# TinyTX4.net
KiCad netlist of a schematic drawn in EAGLE
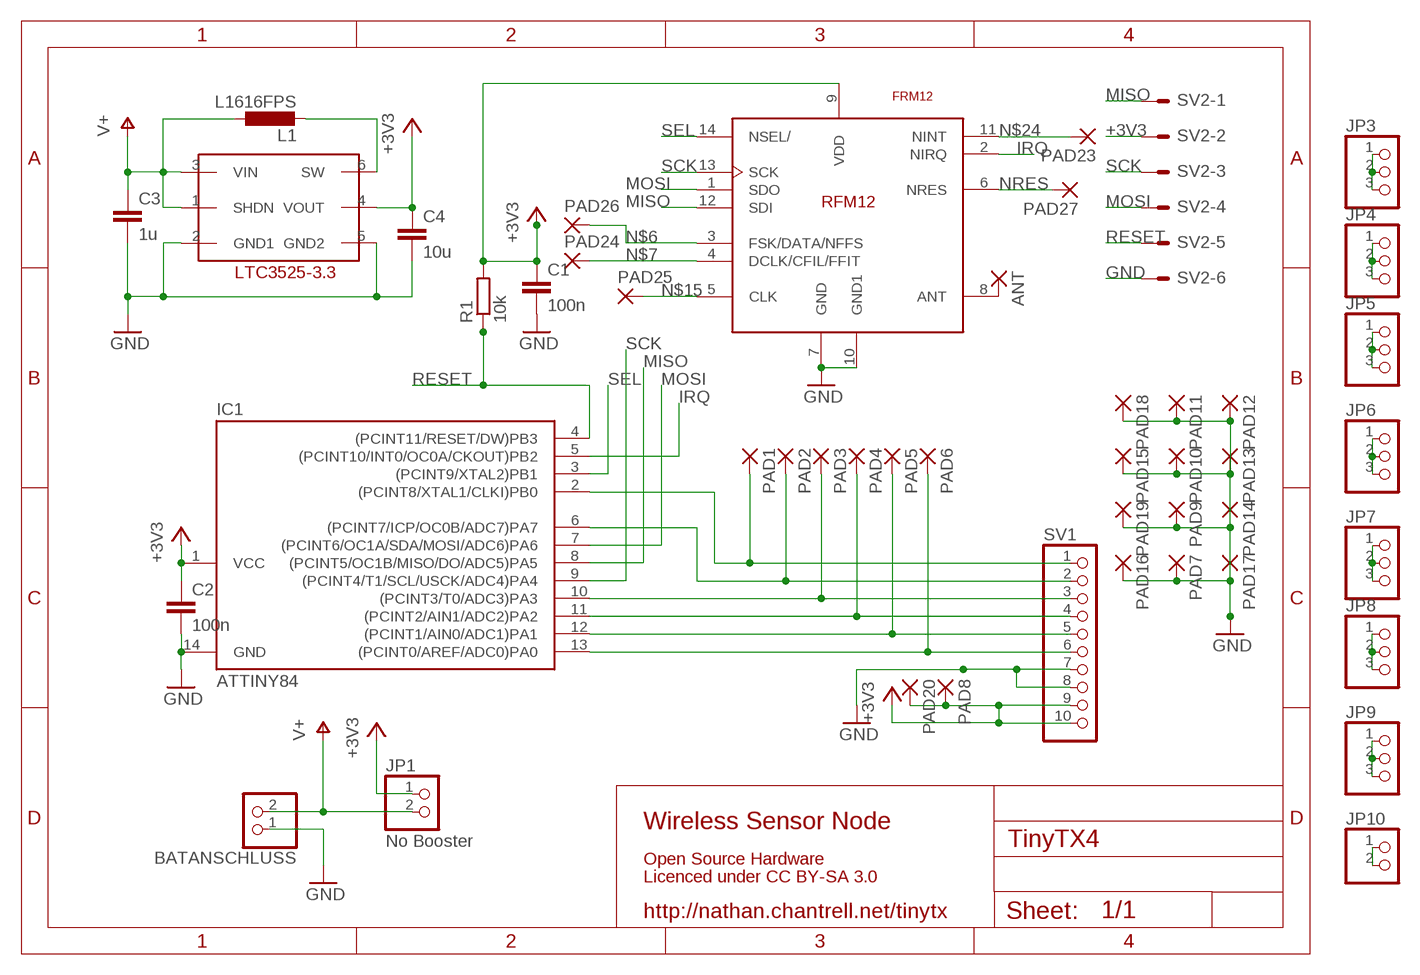
[diagram p0: schematic, sheet 1]

(export (version "E")
  (design (tool "Eeschema 10.0.6"))
  (components
    (comp (ref "ANT")
      (value "1,6/0,8")
      (footprint "eagle-import:1,6_0,8")
      (libsource (lib "eagle-import") (part "1,6/0,8"))
    )
    (comp (ref "BATANSCHLUSS")
      (value "PINHD-1X2")
      (footprint "eagle-import:1X02")
      (libsource (lib "eagle-import") (part "PINHD-1X2"))
    )
    (comp (ref "C1")
      (value "100n")
      (footprint "eagle-import:C0805")
      (libsource (lib "eagle-import") (part "C-EUC0805"))
    )
    (comp (ref "C2")
      (value "100n")
      (footprint "eagle-import:C0805")
      (libsource (lib "eagle-import") (part "C-EUC0805"))
    )
    (comp (ref "C3")
      (value "1u")
      (footprint "eagle-import:C0805")
      (libsource (lib "eagle-import") (part "C-EUC0805"))
    )
    (comp (ref "C4")
      (value "10u")
      (footprint "eagle-import:C0805")
      (libsource (lib "eagle-import") (part "C-EUC0805"))
    )
    (comp (ref "IC1")
      (value "ATTINY84")
      (footprint "eagle-import:SOIC14")
      (libsource (lib "eagle-import") (part "TINY24/44/84-SSU"))
    )
    (comp (ref "IC2")
      (value "IC2")
      (footprint "eagle-import:SC70-6")
      (libsource (lib "eagle-import") (part "LTC3525"))
    )
    (comp (ref "JP1")
      (value "No Booster")
      (footprint "eagle-import:1X02")
      (libsource (lib "eagle-import") (part "PINHD-1X2"))
    )
    (comp (ref "JP3")
      (value "PINHD-1X3")
      (footprint "eagle-import:1X03")
      (libsource (lib "eagle-import") (part "PINHD-1X3"))
    )
    (comp (ref "JP4")
      (value "PINHD-1X3")
      (footprint "eagle-import:1X03")
      (libsource (lib "eagle-import") (part "PINHD-1X3"))
    )
    (comp (ref "JP5")
      (value "PINHD-1X3")
      (footprint "eagle-import:1X03")
      (libsource (lib "eagle-import") (part "PINHD-1X3"))
    )
    (comp (ref "JP6")
      (value "PINHD-1X3")
      (footprint "eagle-import:1X03")
      (libsource (lib "eagle-import") (part "PINHD-1X3"))
    )
    (comp (ref "JP7")
      (value "PINHD-1X3")
      (footprint "eagle-import:1X03")
      (libsource (lib "eagle-import") (part "PINHD-1X3"))
    )
    (comp (ref "JP8")
      (value "PINHD-1X3")
      (footprint "eagle-import:1X03")
      (libsource (lib "eagle-import") (part "PINHD-1X3"))
    )
    (comp (ref "JP9")
      (value "PINHD-1X3")
      (footprint "eagle-import:1X03")
      (libsource (lib "eagle-import") (part "PINHD-1X3"))
    )
    (comp (ref "JP10")
      (value "PINHD-1X2")
      (footprint "eagle-import:1X02")
      (libsource (lib "eagle-import") (part "PINHD-1X2"))
    )
    (comp (ref "L1")
      (value "L1616FPS")
      (footprint "eagle-import:L1616")
      (libsource (lib "eagle-import") (part "L1616FPS"))
    )
    (comp (ref "PAD1")
      (value "1,6/0,9")
      (footprint "eagle-import:1,6_0,9")
      (libsource (lib "eagle-import") (part "1,6/0,9"))
    )
    (comp (ref "PAD2")
      (value "1,6/0,9")
      (footprint "eagle-import:1,6_0,9")
      (libsource (lib "eagle-import") (part "1,6/0,9"))
    )
    (comp (ref "PAD3")
      (value "1,6/0,9")
      (footprint "eagle-import:1,6_0,9")
      (libsource (lib "eagle-import") (part "1,6/0,9"))
    )
    (comp (ref "PAD4")
      (value "1,6/0,9")
      (footprint "eagle-import:1,6_0,9")
      (libsource (lib "eagle-import") (part "1,6/0,9"))
    )
    (comp (ref "PAD5")
      (value "1,6/0,9")
      (footprint "eagle-import:1,6_0,9")
      (libsource (lib "eagle-import") (part "1,6/0,9"))
    )
    (comp (ref "PAD6")
      (value "1,6/0,9")
      (footprint "eagle-import:1,6_0,9")
      (libsource (lib "eagle-import") (part "1,6/0,9"))
    )
    (comp (ref "PAD7")
      (value "1,6/0,9")
      (footprint "eagle-import:1,6_0,9")
      (libsource (lib "eagle-import") (part "1,6/0,9"))
    )
    (comp (ref "PAD8")
      (value "1,6/0,9")
      (footprint "eagle-import:1,6_0,9")
      (libsource (lib "eagle-import") (part "1,6/0,9"))
    )
    (comp (ref "PAD9")
      (value "1,6/0,9")
      (footprint "eagle-import:1,6_0,9")
      (libsource (lib "eagle-import") (part "1,6/0,9"))
    )
    (comp (ref "PAD10")
      (value "1,6/0,9")
      (footprint "eagle-import:1,6_0,9")
      (libsource (lib "eagle-import") (part "1,6/0,9"))
    )
    (comp (ref "PAD11")
      (value "1,6/0,9")
      (footprint "eagle-import:1,6_0,9")
      (libsource (lib "eagle-import") (part "1,6/0,9"))
    )
    (comp (ref "PAD12")
      (value "1,6/0,9")
      (footprint "eagle-import:1,6_0,9")
      (libsource (lib "eagle-import") (part "1,6/0,9"))
    )
    (comp (ref "PAD13")
      (value "1,6/0,9")
      (footprint "eagle-import:1,6_0,9")
      (libsource (lib "eagle-import") (part "1,6/0,9"))
    )
    (comp (ref "PAD14")
      (value "1,6/0,9")
      (footprint "eagle-import:1,6_0,9")
      (libsource (lib "eagle-import") (part "1,6/0,9"))
    )
    (comp (ref "PAD15")
      (value "1,6/0,9")
      (footprint "eagle-import:1,6_0,9")
      (libsource (lib "eagle-import") (part "1,6/0,9"))
    )
    (comp (ref "PAD16")
      (value "1,6/0,9")
      (footprint "eagle-import:1,6_0,9")
      (libsource (lib "eagle-import") (part "1,6/0,9"))
    )
    (comp (ref "PAD17")
      (value "1,6/0,9")
      (footprint "eagle-import:1,6_0,9")
      (libsource (lib "eagle-import") (part "1,6/0,9"))
    )
    (comp (ref "PAD18")
      (value "1,6/0,9")
      (footprint "eagle-import:1,6_0,9")
      (libsource (lib "eagle-import") (part "1,6/0,9"))
    )
    (comp (ref "PAD19")
      (value "1,6/0,9")
      (footprint "eagle-import:1,6_0,9")
      (libsource (lib "eagle-import") (part "1,6/0,9"))
    )
    (comp (ref "PAD20")
      (value "1,6/0,9")
      (footprint "eagle-import:1,6_0,9")
      (libsource (lib "eagle-import") (part "1,6/0,9"))
    )
    (comp (ref "PAD23")
      (value "1,6/0,9")
      (footprint "eagle-import:1,6_0,9")
      (libsource (lib "eagle-import") (part "1,6/0,9"))
    )
    (comp (ref "PAD24")
      (value "1,6/0,9")
      (footprint "eagle-import:1,6_0,9")
      (libsource (lib "eagle-import") (part "1,6/0,9"))
    )
    (comp (ref "PAD25")
      (value "1,6/0,9")
      (footprint "eagle-import:1,6_0,9")
      (libsource (lib "eagle-import") (part "1,6/0,9"))
    )
    (comp (ref "PAD26")
      (value "1,6/0,9")
      (footprint "eagle-import:1,6_0,9")
      (libsource (lib "eagle-import") (part "1,6/0,9"))
    )
    (comp (ref "PAD27")
      (value "1,6/0,9")
      (footprint "eagle-import:1,6_0,9")
      (libsource (lib "eagle-import") (part "1,6/0,9"))
    )
    (comp (ref "R1")
      (value "10k")
      (footprint "eagle-import:R0805")
      (libsource (lib "eagle-import") (part "R-EU_R0805"))
    )
    (comp (ref "SV1")
      (value "PINHD-1X10")
      (footprint "eagle-import:1X10")
      (libsource (lib "eagle-import") (part "PINHD-1X10"))
    )
    (comp (ref "SV2")
      (value "ML6E")
      (footprint "eagle-import:ML6")
      (libsource (lib "eagle-import") (part "ML6?E"))
    )
    (comp (ref "U$3")
      (value "FRM12")
      (footprint "eagle-import:RFM12")
      (libsource (lib "eagle-import") (part "FRM12"))
    )
  )
  (nets
    (net (code "1") (name "+3V3") (class "Default")
      (node (ref "C1") (pin "1") (pinfunction "1_1") (pintype "passive"))
      (node (ref "C2") (pin "1") (pinfunction "1_1") (pintype "passive"))
      (node (ref "C4") (pin "1") (pinfunction "1_1") (pintype "passive"))
      (node (ref "IC1") (pin "1") (pinfunction "VCC_1") (pintype "power_in"))
      (node (ref "IC2") (pin "4") (pinfunction "VOUT_4") (pintype "bidirectional"))
      (node (ref "JP1") (pin "1") (pinfunction "1_1") (pintype "passive"))
      (node (ref "PAD20") (pin "1") (pinfunction "P_1") (pintype "passive"))
      (node (ref "PAD8") (pin "1") (pinfunction "P_1") (pintype "passive"))
      (node (ref "R1") (pin "2") (pinfunction "2_2") (pintype "passive"))
      (node (ref "SV1") (pin "10") (pinfunction "10_10") (pintype "passive"))
      (node (ref "SV1") (pin "9") (pinfunction "9_9") (pintype "passive"))
      (node (ref "SV2") (pin "2") (pinfunction "S_2") (pintype "passive"))
      (node (ref "U$3") (pin "9") (pinfunction "VDD_9") (pintype "power_in"))
    )
    (net (code "2") (name "/IRQ") (class "Default")
      (node (ref "IC1") (pin "5") (pinfunction "(PCINT10/INT0/OC0A/CKOUT)PB2_5") (pintype "bidirectional"))
      (node (ref "U$3") (pin "2") (pinfunction "NIRQ_2") (pintype "output"))
    )
    (net (code "3") (name "/MISO") (class "Default")
      (node (ref "IC1") (pin "8") (pinfunction "(PCINT5/OC1B/MISO/DO/ADC5)PA5_8") (pintype "bidirectional"))
      (node (ref "SV2") (pin "1") (pinfunction "S_1") (pintype "passive"))
      (node (ref "U$3") (pin "12") (pinfunction "SDI_12") (pintype "input"))
    )
    (net (code "4") (name "/MOSI") (class "Default")
      (node (ref "IC1") (pin "7") (pinfunction "(PCINT6/OC1A/SDA/MOSI/ADC6)PA6_7") (pintype "bidirectional"))
      (node (ref "SV2") (pin "4") (pinfunction "S_4") (pintype "passive"))
      (node (ref "U$3") (pin "1") (pinfunction "SDO_1") (pintype "output"))
    )
    (net (code "5") (name "/N$6") (class "Default")
      (node (ref "PAD26") (pin "1") (pinfunction "P_1") (pintype "passive"))
      (node (ref "U$3") (pin "3") (pinfunction "FSK/DATA/NFFS_3") (pintype "bidirectional"))
    )
    (net (code "6") (name "/N$7") (class "Default")
      (node (ref "PAD24") (pin "1") (pinfunction "P_1") (pintype "passive"))
      (node (ref "U$3") (pin "4") (pinfunction "DCLK/CFIL/FFIT_4") (pintype "bidirectional"))
    )
    (net (code "7") (name "/N$15") (class "Default")
      (node (ref "PAD25") (pin "1") (pinfunction "P_1") (pintype "passive"))
      (node (ref "U$3") (pin "5") (pinfunction "CLK_5") (pintype "output"))
    )
    (net (code "8") (name "/N$24") (class "Default")
      (node (ref "PAD23") (pin "1") (pinfunction "P_1") (pintype "passive"))
      (node (ref "U$3") (pin "11") (pinfunction "NINT_11") (pintype "bidirectional"))
    )
    (net (code "9") (name "/NRES") (class "Default")
      (node (ref "PAD27") (pin "1") (pinfunction "P_1") (pintype "passive"))
      (node (ref "U$3") (pin "6") (pinfunction "NRES_6") (pintype "bidirectional"))
    )
    (net (code "10") (name "/RESET") (class "Default")
      (node (ref "IC1") (pin "4") (pinfunction "(PCINT11/RESET/DW)PB3_4") (pintype "bidirectional"))
      (node (ref "R1") (pin "1") (pinfunction "1_1") (pintype "passive"))
      (node (ref "SV2") (pin "5") (pinfunction "S_5") (pintype "passive"))
    )
    (net (code "11") (name "/SCK") (class "Default")
      (node (ref "IC1") (pin "9") (pinfunction "(PCINT4/T1/SCL/USCK/ADC4)PA4_9") (pintype "bidirectional"))
      (node (ref "SV2") (pin "3") (pinfunction "S_3") (pintype "passive"))
      (node (ref "U$3") (pin "13") (pinfunction "SCK_13") (pintype "input"))
    )
    (net (code "12") (name "/SEL") (class "Default")
      (node (ref "IC1") (pin "3") (pinfunction "(PCINT9/XTAL2)PB1_3") (pintype "bidirectional"))
      (node (ref "U$3") (pin "14") (pinfunction "NSEL/_14") (pintype "input"))
    )
    (net (code "13") (name "GND") (class "Default")
      (node (ref "BATANSCHLUSS") (pin "1") (pinfunction "1_1") (pintype "passive"))
      (node (ref "C1") (pin "2") (pinfunction "2_2") (pintype "passive"))
      (node (ref "C2") (pin "2") (pinfunction "2_2") (pintype "passive"))
      (node (ref "C3") (pin "2") (pinfunction "2_2") (pintype "passive"))
      (node (ref "C4") (pin "2") (pinfunction "2_2") (pintype "passive"))
      (node (ref "IC1") (pin "14") (pinfunction "GND_14") (pintype "power_in"))
      (node (ref "IC2") (pin "2") (pinfunction "GND1_2") (pintype "bidirectional"))
      (node (ref "IC2") (pin "5") (pinfunction "GND2_5") (pintype "bidirectional"))
      (node (ref "PAD10") (pin "1") (pinfunction "P_1") (pintype "passive"))
      (node (ref "PAD11") (pin "1") (pinfunction "P_1") (pintype "passive"))
      (node (ref "PAD12") (pin "1") (pinfunction "P_1") (pintype "passive"))
      (node (ref "PAD13") (pin "1") (pinfunction "P_1") (pintype "passive"))
      (node (ref "PAD14") (pin "1") (pinfunction "P_1") (pintype "passive"))
      (node (ref "PAD15") (pin "1") (pinfunction "P_1") (pintype "passive"))
      (node (ref "PAD16") (pin "1") (pinfunction "P_1") (pintype "passive"))
      (node (ref "PAD17") (pin "1") (pinfunction "P_1") (pintype "passive"))
      (node (ref "PAD18") (pin "1") (pinfunction "P_1") (pintype "passive"))
      (node (ref "PAD19") (pin "1") (pinfunction "P_1") (pintype "passive"))
      (node (ref "PAD7") (pin "1") (pinfunction "P_1") (pintype "passive"))
      (node (ref "PAD9") (pin "1") (pinfunction "P_1") (pintype "passive"))
      (node (ref "SV1") (pin "7") (pinfunction "7_7") (pintype "passive"))
      (node (ref "SV1") (pin "8") (pinfunction "8_8") (pintype "passive"))
      (node (ref "SV2") (pin "6") (pinfunction "S_6") (pintype "passive"))
      (node (ref "U$3") (pin "10") (pinfunction "GND1_10") (pintype "passive"))
      (node (ref "U$3") (pin "7") (pinfunction "GND_7") (pintype "passive"))
    )
    (net (code "14") (name "Net-(ANT-P)") (class "Default")
      (node (ref "ANT") (pin "1") (pinfunction "P_1") (pintype "passive"))
      (node (ref "U$3") (pin "8") (pinfunction "ANT_8") (pintype "bidirectional"))
    )
    (net (code "15") (name "Net-(IC1-(PCINT0{slash}AREF{slash}ADC0)PA0)") (class "Default")
      (node (ref "IC1") (pin "13") (pinfunction "(PCINT0/AREF/ADC0)PA0_13") (pintype "bidirectional"))
      (node (ref "PAD6") (pin "1") (pinfunction "P_1") (pintype "passive"))
      (node (ref "SV1") (pin "6") (pinfunction "6_6") (pintype "passive"))
    )
    (net (code "16") (name "Net-(IC1-(PCINT1{slash}AIN0{slash}ADC1)PA1)") (class "Default")
      (node (ref "IC1") (pin "12") (pinfunction "(PCINT1/AIN0/ADC1)PA1_12") (pintype "bidirectional"))
      (node (ref "PAD5") (pin "1") (pinfunction "P_1") (pintype "passive"))
      (node (ref "SV1") (pin "5") (pinfunction "5_5") (pintype "passive"))
    )
    (net (code "17") (name "Net-(IC1-(PCINT2{slash}AIN1{slash}ADC2)PA2)") (class "Default")
      (node (ref "IC1") (pin "11") (pinfunction "(PCINT2/AIN1/ADC2)PA2_11") (pintype "bidirectional"))
      (node (ref "PAD4") (pin "1") (pinfunction "P_1") (pintype "passive"))
      (node (ref "SV1") (pin "4") (pinfunction "4_4") (pintype "passive"))
    )
    (net (code "18") (name "Net-(IC1-(PCINT3{slash}T0{slash}ADC3)PA3)") (class "Default")
      (node (ref "IC1") (pin "10") (pinfunction "(PCINT3/T0/ADC3)PA3_10") (pintype "bidirectional"))
      (node (ref "PAD3") (pin "1") (pinfunction "P_1") (pintype "passive"))
      (node (ref "SV1") (pin "3") (pinfunction "3_3") (pintype "passive"))
    )
    (net (code "19") (name "Net-(IC1-(PCINT7{slash}ICP{slash}OC0B{slash}ADC7)PA7)") (class "Default")
      (node (ref "IC1") (pin "6") (pinfunction "(PCINT7/ICP/OC0B/ADC7)PA7_6") (pintype "bidirectional"))
      (node (ref "PAD2") (pin "1") (pinfunction "P_1") (pintype "passive"))
      (node (ref "SV1") (pin "2") (pinfunction "2_2") (pintype "passive"))
    )
    (net (code "20") (name "Net-(IC1-(PCINT8{slash}XTAL1{slash}CLKI)PB0)") (class "Default")
      (node (ref "IC1") (pin "2") (pinfunction "(PCINT8/XTAL1/CLKI)PB0_2") (pintype "bidirectional"))
      (node (ref "PAD1") (pin "1") (pinfunction "P_1") (pintype "passive"))
      (node (ref "SV1") (pin "1") (pinfunction "1_1") (pintype "passive"))
    )
    (net (code "21") (name "Net-(IC2-SW)") (class "Default")
      (node (ref "IC2") (pin "6") (pinfunction "SW_6") (pintype "bidirectional"))
      (node (ref "L1") (pin "P$2") (pinfunction "2_P$2") (pintype "passive"))
    )
    (net (code "22") (name "Net-(JP3-Pad1)") (class "Default")
      (node (ref "JP3") (pin "1") (pinfunction "1_1") (pintype "passive"))
      (node (ref "JP3") (pin "2") (pinfunction "2_2") (pintype "passive"))
      (node (ref "JP3") (pin "3") (pinfunction "3_3") (pintype "passive"))
    )
    (net (code "23") (name "Net-(JP4-Pad1)") (class "Default")
      (node (ref "JP4") (pin "1") (pinfunction "1_1") (pintype "passive"))
      (node (ref "JP4") (pin "2") (pinfunction "2_2") (pintype "passive"))
      (node (ref "JP4") (pin "3") (pinfunction "3_3") (pintype "passive"))
    )
    (net (code "24") (name "Net-(JP5-Pad1)") (class "Default")
      (node (ref "JP5") (pin "1") (pinfunction "1_1") (pintype "passive"))
      (node (ref "JP5") (pin "2") (pinfunction "2_2") (pintype "passive"))
      (node (ref "JP5") (pin "3") (pinfunction "3_3") (pintype "passive"))
    )
    (net (code "25") (name "Net-(JP6-Pad1)") (class "Default")
      (node (ref "JP6") (pin "1") (pinfunction "1_1") (pintype "passive"))
      (node (ref "JP6") (pin "2") (pinfunction "2_2") (pintype "passive"))
      (node (ref "JP6") (pin "3") (pinfunction "3_3") (pintype "passive"))
    )
    (net (code "26") (name "Net-(JP7-Pad1)") (class "Default")
      (node (ref "JP7") (pin "1") (pinfunction "1_1") (pintype "passive"))
      (node (ref "JP7") (pin "2") (pinfunction "2_2") (pintype "passive"))
      (node (ref "JP7") (pin "3") (pinfunction "3_3") (pintype "passive"))
    )
    (net (code "27") (name "Net-(JP8-Pad1)") (class "Default")
      (node (ref "JP8") (pin "1") (pinfunction "1_1") (pintype "passive"))
      (node (ref "JP8") (pin "2") (pinfunction "2_2") (pintype "passive"))
      (node (ref "JP8") (pin "3") (pinfunction "3_3") (pintype "passive"))
    )
    (net (code "28") (name "Net-(JP9-Pad1)") (class "Default")
      (node (ref "JP9") (pin "1") (pinfunction "1_1") (pintype "passive"))
      (node (ref "JP9") (pin "2") (pinfunction "2_2") (pintype "passive"))
      (node (ref "JP9") (pin "3") (pinfunction "3_3") (pintype "passive"))
    )
    (net (code "29") (name "Net-(JP10-Pad1)") (class "Default")
      (node (ref "JP10") (pin "1") (pinfunction "1_1") (pintype "passive"))
      (node (ref "JP10") (pin "2") (pinfunction "2_2") (pintype "passive"))
    )
    (net (code "30") (name "V+") (class "Default")
      (node (ref "BATANSCHLUSS") (pin "2") (pinfunction "2_2") (pintype "passive"))
      (node (ref "C3") (pin "1") (pinfunction "1_1") (pintype "passive"))
      (node (ref "IC2") (pin "1") (pinfunction "SHDN_1") (pintype "bidirectional"))
      (node (ref "IC2") (pin "3") (pinfunction "VIN_3") (pintype "bidirectional"))
      (node (ref "JP1") (pin "2") (pinfunction "2_2") (pintype "passive"))
      (node (ref "L1") (pin "P$1") (pinfunction "1_P$1") (pintype "passive"))
    )
  )
)
